# kolrs868_rx.net
KiCad netlist of a schematic drawn in EAGLE
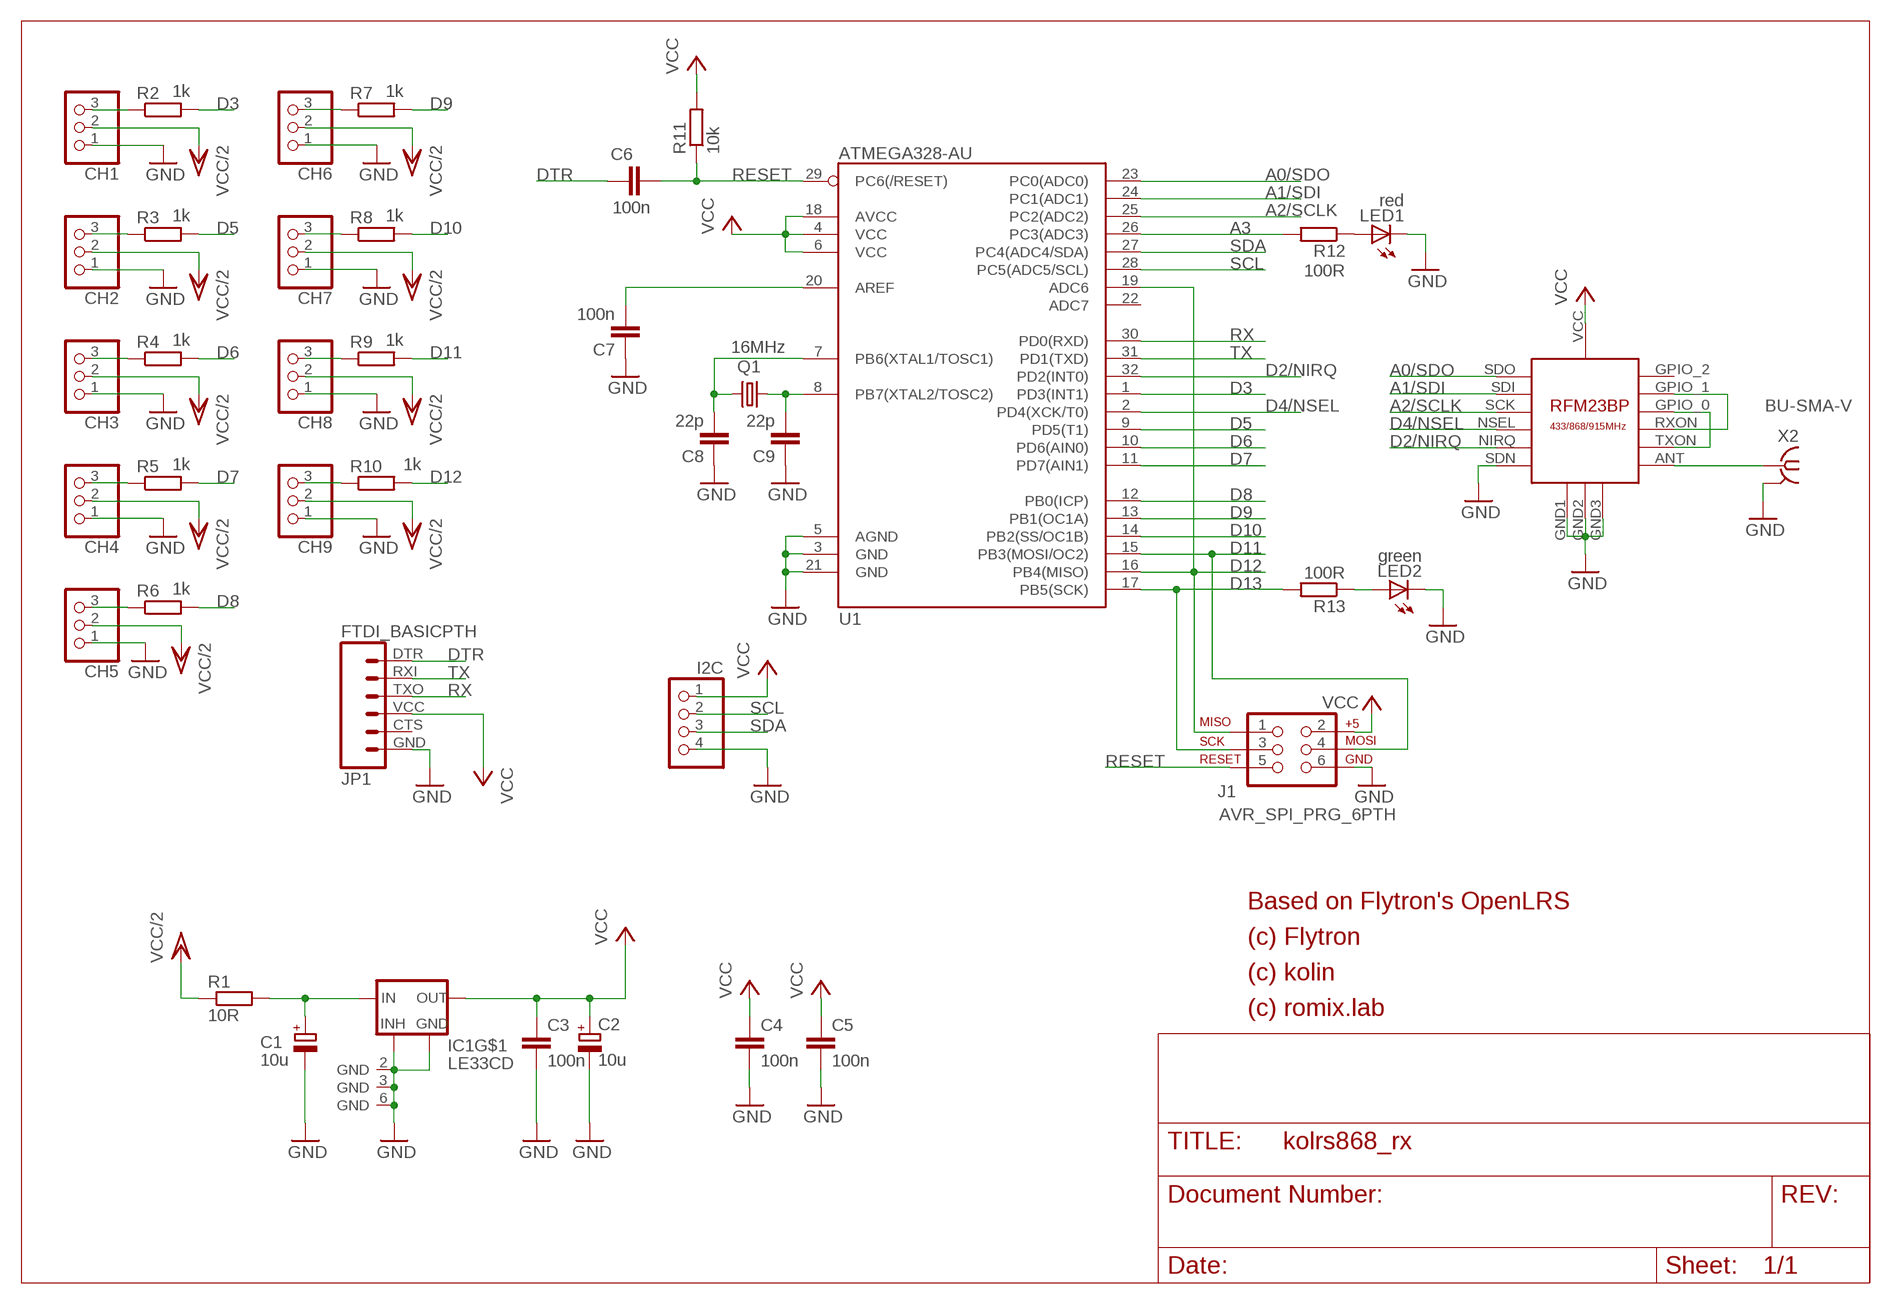
[diagram p0: schematic, sheet 1]

(export (version "E")
  (design (tool "Eeschema 10.0.6"))
  (components
    (comp (ref "C1")
      (value "10u")
      (footprint "eagle-import:SMC_B")
      (libsource (lib "eagle-import") (part "CPOL-EUSMCB"))
    )
    (comp (ref "C2")
      (value "10u")
      (footprint "eagle-import:SMC_B")
      (libsource (lib "eagle-import") (part "CPOL-EUSMCB"))
    )
    (comp (ref "C3")
      (value "100n")
      (footprint "eagle-import:M0805")
      (libsource (lib "eagle-import") (part "C-EU_KOLIN"))
    )
    (comp (ref "C4")
      (value "100n")
      (footprint "eagle-import:M0805")
      (libsource (lib "eagle-import") (part "C-EU_KOLIN"))
    )
    (comp (ref "C5")
      (value "100n")
      (footprint "eagle-import:M0805")
      (libsource (lib "eagle-import") (part "C-EU_KOLIN"))
    )
    (comp (ref "C6")
      (value "100n")
      (footprint "eagle-import:M0805")
      (libsource (lib "eagle-import") (part "C-EU_KOLIN"))
    )
    (comp (ref "C7")
      (value "100n")
      (footprint "eagle-import:M0805")
      (libsource (lib "eagle-import") (part "C-EU_KOLIN"))
    )
    (comp (ref "C8")
      (value "22p")
      (footprint "eagle-import:M0805")
      (libsource (lib "eagle-import") (part "C-EU_KOLIN"))
    )
    (comp (ref "C9")
      (value "22p")
      (footprint "eagle-import:M0805")
      (libsource (lib "eagle-import") (part "C-EU_KOLIN"))
    )
    (comp (ref "CH1")
      (value "PINHD-1X3_KOLINOVO")
      (footprint "eagle-import:1X03")
      (libsource (lib "eagle-import") (part "PINHD-1X3_KOLINOVO"))
    )
    (comp (ref "CH2")
      (value "PINHD-1X3_KOLINOVO")
      (footprint "eagle-import:1X03")
      (libsource (lib "eagle-import") (part "PINHD-1X3_KOLINOVO"))
    )
    (comp (ref "CH3")
      (value "PINHD-1X3_KOLINOVO")
      (footprint "eagle-import:1X03")
      (libsource (lib "eagle-import") (part "PINHD-1X3_KOLINOVO"))
    )
    (comp (ref "CH4")
      (value "PINHD-1X3_KOLINOVO")
      (footprint "eagle-import:1X03")
      (libsource (lib "eagle-import") (part "PINHD-1X3_KOLINOVO"))
    )
    (comp (ref "CH5")
      (value "PINHD-1X3_KOLINOVO")
      (footprint "eagle-import:1X03")
      (libsource (lib "eagle-import") (part "PINHD-1X3_KOLINOVO"))
    )
    (comp (ref "CH6")
      (value "PINHD-1X3_KOLINOVO")
      (footprint "eagle-import:1X03")
      (libsource (lib "eagle-import") (part "PINHD-1X3_KOLINOVO"))
    )
    (comp (ref "CH7")
      (value "PINHD-1X3_KOLINOVO")
      (footprint "eagle-import:1X03")
      (libsource (lib "eagle-import") (part "PINHD-1X3_KOLINOVO"))
    )
    (comp (ref "CH8")
      (value "PINHD-1X3_KOLINOVO")
      (footprint "eagle-import:1X03")
      (libsource (lib "eagle-import") (part "PINHD-1X3_KOLINOVO"))
    )
    (comp (ref "CH9")
      (value "PINHD-1X3_KOLINOVO")
      (footprint "eagle-import:1X03")
      (libsource (lib "eagle-import") (part "PINHD-1X3_KOLINOVO"))
    )
    (comp (ref "I2C")
      (value "PINHD-1X4")
      (footprint "eagle-import:1X04")
      (libsource (lib "eagle-import") (part "PINHD-1X4"))
    )
    (comp (ref "IC1")
      (value "LE33CD")
      (footprint "eagle-import:SO8")
      (libsource (lib "eagle-import") (part "LE33CD"))
    )
    (comp (ref "J1")
      (value "AVR_SPI_PRG_6PTH")
      (footprint "eagle-import:2X3")
      (libsource (lib "eagle-import") (part "AVR_SPI_PRG_6PTH"))
    )
    (comp (ref "JP1")
      (value "FTDI_BASICPTH")
      (footprint "eagle-import:FTDI_BASIC")
      (libsource (lib "eagle-import") (part "FTDI_BASICPTH"))
    )
    (comp (ref "LED1")
      (value "red")
      (footprint "eagle-import:CHIPLED_0805")
      (libsource (lib "eagle-import") (part "LEDCHIPLED_0805"))
    )
    (comp (ref "LED2")
      (value "green")
      (footprint "eagle-import:CHIPLED_0805")
      (libsource (lib "eagle-import") (part "LEDCHIPLED_0805"))
    )
    (comp (ref "Q1")
      (value "16MHz")
      (footprint "eagle-import:HC49UP")
      (libsource (lib "eagle-import") (part "CRYSTALHC49UP"))
    )
    (comp (ref "R1")
      (value "10R")
      (footprint "eagle-import:M0805")
      (libsource (lib "eagle-import") (part "R-EU_KOLINM0805"))
    )
    (comp (ref "R2")
      (value "1k")
      (footprint "eagle-import:M0805")
      (libsource (lib "eagle-import") (part "R-EU_KOLINM0805"))
    )
    (comp (ref "R3")
      (value "1k")
      (footprint "eagle-import:M0805")
      (libsource (lib "eagle-import") (part "R-EU_KOLINM0805"))
    )
    (comp (ref "R4")
      (value "1k")
      (footprint "eagle-import:M0805")
      (libsource (lib "eagle-import") (part "R-EU_KOLINM0805"))
    )
    (comp (ref "R5")
      (value "1k")
      (footprint "eagle-import:M0805")
      (libsource (lib "eagle-import") (part "R-EU_KOLINM0805"))
    )
    (comp (ref "R6")
      (value "1k")
      (footprint "eagle-import:M0805")
      (libsource (lib "eagle-import") (part "R-EU_KOLINM0805"))
    )
    (comp (ref "R7")
      (value "1k")
      (footprint "eagle-import:M0805")
      (libsource (lib "eagle-import") (part "R-EU_KOLINM0805"))
    )
    (comp (ref "R8")
      (value "1k")
      (footprint "eagle-import:M0805")
      (libsource (lib "eagle-import") (part "R-EU_KOLINM0805"))
    )
    (comp (ref "R9")
      (value "1k")
      (footprint "eagle-import:M0805")
      (libsource (lib "eagle-import") (part "R-EU_KOLINM0805"))
    )
    (comp (ref "R10")
      (value "1k")
      (footprint "eagle-import:M0805")
      (libsource (lib "eagle-import") (part "R-EU_KOLINM0805"))
    )
    (comp (ref "R11")
      (value "10k")
      (footprint "eagle-import:M0805")
      (libsource (lib "eagle-import") (part "R-EU_KOLINM0805"))
    )
    (comp (ref "R12")
      (value "100R")
      (footprint "eagle-import:M0805")
      (libsource (lib "eagle-import") (part "R-EU_KOLINM0805"))
    )
    (comp (ref "R13")
      (value "100R")
      (footprint "eagle-import:M0805")
      (libsource (lib "eagle-import") (part "R-EU_KOLINM0805"))
    )
    (comp (ref "U$1")
      (value "RFM23BP")
      (footprint "eagle-import:RFM23BP")
      (libsource (lib "eagle-import") (part "RFM23BP"))
    )
    (comp (ref "U1")
      (value "ATMEGA328-AU")
      (footprint "eagle-import:TQFP32-08")
      (libsource (lib "eagle-import") (part "ATMEGA168"))
    )
    (comp (ref "X2")
      (value "BU-SMA-V")
      (footprint "eagle-import:BU-SMA-V")
      (libsource (lib "eagle-import") (part "BU-SMA-V"))
    )
  )
  (nets
    (net (code "1") (name "/A0{slash}SDO") (class "Default")
      (node (ref "U$1") (pin "SDO") (pinfunction "SDO_SDO") (pintype "bidirectional"))
      (node (ref "U1") (pin "23") (pinfunction "PC0(ADC0)_23") (pintype "bidirectional"))
    )
    (net (code "2") (name "/A1{slash}SDI") (class "Default")
      (node (ref "U$1") (pin "SDI") (pinfunction "SDI_SDI") (pintype "bidirectional"))
      (node (ref "U1") (pin "24") (pinfunction "PC1(ADC1)_24") (pintype "bidirectional"))
    )
    (net (code "3") (name "/A2{slash}SCLK") (class "Default")
      (node (ref "U$1") (pin "SCK") (pinfunction "SCK_SCK") (pintype "bidirectional"))
      (node (ref "U1") (pin "25") (pinfunction "PC2(ADC2)_25") (pintype "bidirectional"))
    )
    (net (code "4") (name "/A3") (class "Default")
      (node (ref "R12") (pin "2") (pinfunction "2_2") (pintype "passive"))
      (node (ref "U1") (pin "26") (pinfunction "PC3(ADC3)_26") (pintype "bidirectional"))
    )
    (net (code "5") (name "/D2{slash}NIRQ") (class "Default")
      (node (ref "U$1") (pin "NIRQ") (pinfunction "NIRQ_NIRQ") (pintype "bidirectional"))
      (node (ref "U1") (pin "32") (pinfunction "PD2(INT0)_32") (pintype "bidirectional"))
    )
    (net (code "6") (name "/D3") (class "Default")
      (node (ref "R2") (pin "2") (pinfunction "2_2") (pintype "passive"))
      (node (ref "U1") (pin "1") (pinfunction "PD3(INT1)_1") (pintype "bidirectional"))
    )
    (net (code "7") (name "/D4{slash}NSEL") (class "Default")
      (node (ref "U$1") (pin "NSEL") (pinfunction "NSEL_NSEL") (pintype "bidirectional"))
      (node (ref "U1") (pin "2") (pinfunction "PD4(XCK/T0)_2") (pintype "bidirectional"))
    )
    (net (code "8") (name "/D5") (class "Default")
      (node (ref "R3") (pin "2") (pinfunction "2_2") (pintype "passive"))
      (node (ref "U1") (pin "9") (pinfunction "PD5(T1)_9") (pintype "bidirectional"))
    )
    (net (code "9") (name "/D6") (class "Default")
      (node (ref "R4") (pin "2") (pinfunction "2_2") (pintype "passive"))
      (node (ref "U1") (pin "10") (pinfunction "PD6(AIN0)_10") (pintype "bidirectional"))
    )
    (net (code "10") (name "/D7") (class "Default")
      (node (ref "R5") (pin "2") (pinfunction "2_2") (pintype "passive"))
      (node (ref "U1") (pin "11") (pinfunction "PD7(AIN1)_11") (pintype "bidirectional"))
    )
    (net (code "11") (name "/D8") (class "Default")
      (node (ref "R6") (pin "2") (pinfunction "2_2") (pintype "passive"))
      (node (ref "U1") (pin "12") (pinfunction "PB0(ICP)_12") (pintype "bidirectional"))
    )
    (net (code "12") (name "/D9") (class "Default")
      (node (ref "R7") (pin "2") (pinfunction "2_2") (pintype "passive"))
      (node (ref "U1") (pin "13") (pinfunction "PB1(OC1A)_13") (pintype "bidirectional"))
    )
    (net (code "13") (name "/D10") (class "Default")
      (node (ref "R8") (pin "2") (pinfunction "2_2") (pintype "passive"))
      (node (ref "U1") (pin "14") (pinfunction "PB2(SS/OC1B)_14") (pintype "bidirectional"))
    )
    (net (code "14") (name "/D11") (class "Default")
      (node (ref "J1") (pin "4") (pinfunction "4_4") (pintype "passive"))
      (node (ref "R9") (pin "2") (pinfunction "2_2") (pintype "passive"))
      (node (ref "U1") (pin "15") (pinfunction "PB3(MOSI/OC2)_15") (pintype "bidirectional"))
    )
    (net (code "15") (name "/D12") (class "Default")
      (node (ref "J1") (pin "1") (pinfunction "1_1") (pintype "passive"))
      (node (ref "R10") (pin "2") (pinfunction "2_2") (pintype "passive"))
      (node (ref "U1") (pin "16") (pinfunction "PB4(MISO)_16") (pintype "bidirectional"))
      (node (ref "U1") (pin "19") (pinfunction "ADC6_19") (pintype "bidirectional"))
    )
    (net (code "16") (name "/D13") (class "Default")
      (node (ref "J1") (pin "3") (pinfunction "3_3") (pintype "passive"))
      (node (ref "R13") (pin "2") (pinfunction "2_2") (pintype "passive"))
      (node (ref "U1") (pin "17") (pinfunction "PB5(SCK)_17") (pintype "bidirectional"))
    )
    (net (code "17") (name "/DTR") (class "Default")
      (node (ref "C6") (pin "1") (pinfunction "1_1") (pintype "passive"))
      (node (ref "JP1") (pin "DTR") (pinfunction "1_DTR") (pintype "passive"))
    )
    (net (code "18") (name "/RESET") (class "Default")
      (node (ref "C6") (pin "2") (pinfunction "2_2") (pintype "passive"))
      (node (ref "J1") (pin "5") (pinfunction "5_5") (pintype "passive"))
      (node (ref "R11") (pin "1") (pinfunction "1_1") (pintype "passive"))
      (node (ref "U1") (pin "29") (pinfunction "PC6(/RESET)_29") (pintype "bidirectional"))
    )
    (net (code "19") (name "/RX") (class "Default")
      (node (ref "JP1") (pin "TXO") (pinfunction "3_TXO") (pintype "passive"))
      (node (ref "U1") (pin "30") (pinfunction "PD0(RXD)_30") (pintype "bidirectional"))
    )
    (net (code "20") (name "/SCL") (class "Default")
      (node (ref "I2C") (pin "2") (pinfunction "2_2") (pintype "passive"))
      (node (ref "U1") (pin "28") (pinfunction "PC5(ADC5/SCL)_28") (pintype "bidirectional"))
    )
    (net (code "21") (name "/SDA") (class "Default")
      (node (ref "I2C") (pin "3") (pinfunction "3_3") (pintype "passive"))
      (node (ref "U1") (pin "27") (pinfunction "PC4(ADC4/SDA)_27") (pintype "bidirectional"))
    )
    (net (code "22") (name "/TX") (class "Default")
      (node (ref "JP1") (pin "RXI") (pinfunction "2_RXI") (pintype "passive"))
      (node (ref "U1") (pin "31") (pinfunction "PD1(TXD)_31") (pintype "bidirectional"))
    )
    (net (code "23") (name "GND") (class "Default")
      (node (ref "C1") (pin "-") (pinfunction "-_-") (pintype "passive"))
      (node (ref "C2") (pin "-") (pinfunction "-_-") (pintype "passive"))
      (node (ref "C3") (pin "2") (pinfunction "2_2") (pintype "passive"))
      (node (ref "C4") (pin "2") (pinfunction "2_2") (pintype "passive"))
      (node (ref "C5") (pin "2") (pinfunction "2_2") (pintype "passive"))
      (node (ref "C7") (pin "1") (pinfunction "1_1") (pintype "passive"))
      (node (ref "C8") (pin "1") (pinfunction "1_1") (pintype "passive"))
      (node (ref "C9") (pin "1") (pinfunction "1_1") (pintype "passive"))
      (node (ref "CH1") (pin "1") (pinfunction "1_1") (pintype "passive"))
      (node (ref "CH2") (pin "1") (pinfunction "1_1") (pintype "passive"))
      (node (ref "CH3") (pin "1") (pinfunction "1_1") (pintype "passive"))
      (node (ref "CH4") (pin "1") (pinfunction "1_1") (pintype "passive"))
      (node (ref "CH5") (pin "1") (pinfunction "1_1") (pintype "passive"))
      (node (ref "CH6") (pin "1") (pinfunction "1_1") (pintype "passive"))
      (node (ref "CH7") (pin "1") (pinfunction "1_1") (pintype "passive"))
      (node (ref "CH8") (pin "1") (pinfunction "1_1") (pintype "passive"))
      (node (ref "CH9") (pin "1") (pinfunction "1_1") (pintype "passive"))
      (node (ref "I2C") (pin "4") (pinfunction "4_4") (pintype "passive"))
      (node (ref "IC1") (pin "2") (pinfunction "GND_2") (pintype "power_in"))
      (node (ref "IC1") (pin "3") (pinfunction "GND_3") (pintype "power_in"))
      (node (ref "IC1") (pin "5") (pinfunction "INHIBIT_5") (pintype "input"))
      (node (ref "IC1") (pin "6") (pinfunction "GND_6") (pintype "power_in"))
      (node (ref "IC1") (pin "7") (pinfunction "GND_7") (pintype "input"))
      (node (ref "J1") (pin "6") (pinfunction "6_6") (pintype "passive"))
      (node (ref "JP1") (pin "GND") (pinfunction "6_GND") (pintype "passive"))
      (node (ref "LED1") (pin "C") (pinfunction "C_C") (pintype "passive"))
      (node (ref "LED2") (pin "C") (pinfunction "C_C") (pintype "passive"))
      (node (ref "U$1") (pin "GND1") (pinfunction "GND1_GND1") (pintype "power_in"))
      (node (ref "U$1") (pin "GND2") (pinfunction "GND2_GND2") (pintype "power_in"))
      (node (ref "U$1") (pin "GND3") (pinfunction "GND3_GND3") (pintype "power_in"))
      (node (ref "U$1") (pin "SDN") (pinfunction "SDN_SDN") (pintype "bidirectional"))
      (node (ref "U1") (pin "21") (pinfunction "GND_21") (pintype "bidirectional"))
      (node (ref "U1") (pin "3") (pinfunction "GND_3") (pintype "bidirectional"))
      (node (ref "U1") (pin "5") (pinfunction "AGND_5") (pintype "bidirectional"))
      (node (ref "X2") (pin "2") (pinfunction "GND_2") (pintype "power_in"))
    )
    (net (code "24") (name "Net-(CH1-Pad3)") (class "Default")
      (node (ref "CH1") (pin "3") (pinfunction "3_3") (pintype "passive"))
      (node (ref "R2") (pin "1") (pinfunction "1_1") (pintype "passive"))
    )
    (net (code "25") (name "Net-(CH2-Pad3)") (class "Default")
      (node (ref "CH2") (pin "3") (pinfunction "3_3") (pintype "passive"))
      (node (ref "R3") (pin "1") (pinfunction "1_1") (pintype "passive"))
    )
    (net (code "26") (name "Net-(CH3-Pad3)") (class "Default")
      (node (ref "CH3") (pin "3") (pinfunction "3_3") (pintype "passive"))
      (node (ref "R4") (pin "1") (pinfunction "1_1") (pintype "passive"))
    )
    (net (code "27") (name "Net-(CH4-Pad3)") (class "Default")
      (node (ref "CH4") (pin "3") (pinfunction "3_3") (pintype "passive"))
      (node (ref "R5") (pin "1") (pinfunction "1_1") (pintype "passive"))
    )
    (net (code "28") (name "Net-(CH5-Pad3)") (class "Default")
      (node (ref "CH5") (pin "3") (pinfunction "3_3") (pintype "passive"))
      (node (ref "R6") (pin "1") (pinfunction "1_1") (pintype "passive"))
    )
    (net (code "29") (name "Net-(CH6-Pad3)") (class "Default")
      (node (ref "CH6") (pin "3") (pinfunction "3_3") (pintype "passive"))
      (node (ref "R7") (pin "1") (pinfunction "1_1") (pintype "passive"))
    )
    (net (code "30") (name "Net-(CH7-Pad3)") (class "Default")
      (node (ref "CH7") (pin "3") (pinfunction "3_3") (pintype "passive"))
      (node (ref "R8") (pin "1") (pinfunction "1_1") (pintype "passive"))
    )
    (net (code "31") (name "Net-(CH8-Pad3)") (class "Default")
      (node (ref "CH8") (pin "3") (pinfunction "3_3") (pintype "passive"))
      (node (ref "R9") (pin "1") (pinfunction "1_1") (pintype "passive"))
    )
    (net (code "32") (name "Net-(CH9-Pad3)") (class "Default")
      (node (ref "CH9") (pin "3") (pinfunction "3_3") (pintype "passive"))
      (node (ref "R10") (pin "1") (pinfunction "1_1") (pintype "passive"))
    )
    (net (code "33") (name "Net-(IC1A-IN)") (class "Default")
      (node (ref "C1") (pin "+") (pinfunction "+_+") (pintype "passive"))
      (node (ref "IC1") (pin "8") (pinfunction "IN_8") (pintype "input"))
      (node (ref "R1") (pin "2") (pinfunction "2_2") (pintype "passive"))
    )
    (net (code "34") (name "Net-(LED1-PadA)") (class "Default")
      (node (ref "LED1") (pin "A") (pinfunction "A_A") (pintype "passive"))
      (node (ref "R12") (pin "1") (pinfunction "1_1") (pintype "passive"))
    )
    (net (code "35") (name "Net-(LED2-PadA)") (class "Default")
      (node (ref "LED2") (pin "A") (pinfunction "A_A") (pintype "passive"))
      (node (ref "R13") (pin "1") (pinfunction "1_1") (pintype "passive"))
    )
    (net (code "36") (name "Net-(U$1-PadANT)") (class "Default")
      (node (ref "U$1") (pin "ANT") (pinfunction "ANT_ANT") (pintype "bidirectional"))
      (node (ref "X2") (pin "1") (pinfunction "1_1") (pintype "passive"))
    )
    (net (code "37") (name "Net-(U$1-PadGPIO_0)") (class "Default")
      (node (ref "U$1") (pin "GPIO_0") (pinfunction "GPIO_0_GPIO_0") (pintype "bidirectional"))
      (node (ref "U$1") (pin "TXON") (pinfunction "TXON_TXON") (pintype "bidirectional"))
    )
    (net (code "38") (name "Net-(U$1-PadGPIO_1)") (class "Default")
      (node (ref "U$1") (pin "GPIO_1") (pinfunction "GPIO_1_GPIO_1") (pintype "bidirectional"))
      (node (ref "U$1") (pin "RXON") (pinfunction "RXON_RXON") (pintype "bidirectional"))
    )
    (net (code "39") (name "Net-(U1-AREF)") (class "Default")
      (node (ref "C7") (pin "2") (pinfunction "2_2") (pintype "passive"))
      (node (ref "U1") (pin "20") (pinfunction "AREF_20") (pintype "bidirectional"))
    )
    (net (code "40") (name "Net-(U1-PB6(XTAL1{slash}TOSC1))") (class "Default")
      (node (ref "C8") (pin "2") (pinfunction "2_2") (pintype "passive"))
      (node (ref "Q1") (pin "2") (pinfunction "2_2") (pintype "passive"))
      (node (ref "U1") (pin "7") (pinfunction "PB6(XTAL1/TOSC1)_7") (pintype "bidirectional"))
    )
    (net (code "41") (name "Net-(U1-PB7(XTAL2{slash}TOSC2))") (class "Default")
      (node (ref "C9") (pin "2") (pinfunction "2_2") (pintype "passive"))
      (node (ref "Q1") (pin "1") (pinfunction "1_1") (pintype "passive"))
      (node (ref "U1") (pin "8") (pinfunction "PB7(XTAL2/TOSC2)_8") (pintype "bidirectional"))
    )
    (net (code "42") (name "VCC") (class "Default")
      (node (ref "C2") (pin "+") (pinfunction "+_+") (pintype "passive"))
      (node (ref "C3") (pin "1") (pinfunction "1_1") (pintype "passive"))
      (node (ref "C4") (pin "1") (pinfunction "1_1") (pintype "passive"))
      (node (ref "C5") (pin "1") (pinfunction "1_1") (pintype "passive"))
      (node (ref "I2C") (pin "1") (pinfunction "1_1") (pintype "passive"))
      (node (ref "IC1") (pin "1") (pinfunction "OUT_1") (pintype "passive"))
      (node (ref "J1") (pin "2") (pinfunction "2_2") (pintype "passive"))
      (node (ref "JP1") (pin "VCC") (pinfunction "4_VCC") (pintype "passive"))
      (node (ref "R11") (pin "2") (pinfunction "2_2") (pintype "passive"))
      (node (ref "U$1") (pin "VCC") (pinfunction "VCC_VCC") (pintype "power_in"))
      (node (ref "U1") (pin "18") (pinfunction "AVCC_18") (pintype "bidirectional"))
      (node (ref "U1") (pin "4") (pinfunction "VCC_4") (pintype "bidirectional"))
      (node (ref "U1") (pin "6") (pinfunction "VCC_6") (pintype "bidirectional"))
    )
    (net (code "43") (name "VCC{slash}2") (class "Default")
      (node (ref "CH1") (pin "2") (pinfunction "2_2") (pintype "passive"))
      (node (ref "CH2") (pin "2") (pinfunction "2_2") (pintype "passive"))
      (node (ref "CH3") (pin "2") (pinfunction "2_2") (pintype "passive"))
      (node (ref "CH4") (pin "2") (pinfunction "2_2") (pintype "passive"))
      (node (ref "CH5") (pin "2") (pinfunction "2_2") (pintype "passive"))
      (node (ref "CH6") (pin "2") (pinfunction "2_2") (pintype "passive"))
      (node (ref "CH7") (pin "2") (pinfunction "2_2") (pintype "passive"))
      (node (ref "CH8") (pin "2") (pinfunction "2_2") (pintype "passive"))
      (node (ref "CH9") (pin "2") (pinfunction "2_2") (pintype "passive"))
      (node (ref "R1") (pin "1") (pinfunction "1_1") (pintype "passive"))
    )
    (net (code "44") (name "unconnected-(JP1-5-PadCTS)") (class "Default")
      (node (ref "JP1") (pin "CTS") (pinfunction "5_CTS") (pintype "passive"))
    )
    (net (code "45") (name "unconnected-(U$1-PadGPIO_2)") (class "Default")
      (node (ref "U$1") (pin "GPIO_2") (pinfunction "GPIO_2_GPIO_2") (pintype "bidirectional"))
    )
    (net (code "46") (name "unconnected-(U1-ADC7-Pad22)") (class "Default")
      (node (ref "U1") (pin "22") (pinfunction "ADC7_22") (pintype "bidirectional"))
    )
  )
)
